# VLC_TX.net
KiCad netlist of a schematic drawn in Altium Designer
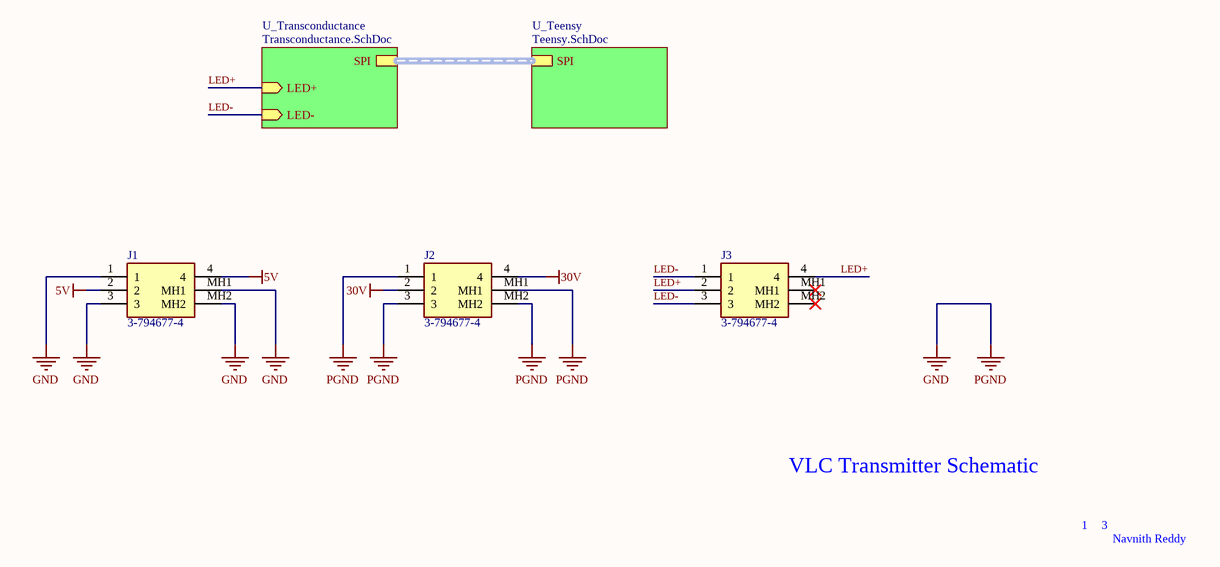
[diagram p0: VLC_TX.SchDoc]

(export (version "E")
  (design (tool "Eeschema 10.0.6"))
  (components
    (comp (ref "J1")
      (value "3-794677-4")
      (footprint "VLC_TX:37946774")
      (description "Connector")
      (fields (field (name "MOUSER PART NUMBER") "571-3-794677-4"))
      (libsource (lib "VLC_TX") (part "3-794677-4"))
    )
    (comp (ref "J2")
      (value "3-794677-4")
      (footprint "VLC_TX:37946774")
      (description "Connector")
      (fields (field (name "MOUSER PART NUMBER") "571-3-794677-4"))
      (libsource (lib "VLC_TX") (part "3-794677-4"))
    )
    (comp (ref "J3")
      (value "3-794677-4")
      (footprint "VLC_TX:37946774")
      (description "Connector")
      (fields (field (name "MOUSER PART NUMBER") "571-3-794677-4"))
      (libsource (lib "VLC_TX") (part "3-794677-4"))
    )
  )
  (nets
    (net (code "1") (name "/LED+") (class "Default")
      (node (ref "J3") (pin "2") (pinfunction "2_2") (pintype "passive"))
      (node (ref "J3") (pin "4") (pinfunction "4_4") (pintype "passive"))
    )
    (net (code "2") (name "/LED-") (class "Default")
      (node (ref "J3") (pin "1") (pinfunction "1_1") (pintype "passive"))
      (node (ref "J3") (pin "3") (pinfunction "3_3") (pintype "passive"))
    )
    (net (code "4") (name "5V") (class "Default")
      (node (ref "J1") (pin "2") (pinfunction "2_2") (pintype "passive"))
      (node (ref "J1") (pin "4") (pinfunction "4_4") (pintype "passive"))
    )
    (net (code "5") (name "30V") (class "Default")
      (node (ref "J2") (pin "2") (pinfunction "2_2") (pintype "passive"))
      (node (ref "J2") (pin "4") (pinfunction "4_4") (pintype "passive"))
    )
    (net (code "6") (name "GND") (class "Default")
      (node (ref "J1") (pin "1") (pinfunction "1_1") (pintype "passive"))
      (node (ref "J1") (pin "3") (pinfunction "3_3") (pintype "passive"))
      (node (ref "J1") (pin "MH1") (pinfunction "MH1_MH1") (pintype "passive"))
      (node (ref "J1") (pin "MH2") (pinfunction "MH2_MH2") (pintype "passive"))
      (node (ref "J2") (pin "1") (pinfunction "1_1") (pintype "passive"))
      (node (ref "J2") (pin "3") (pinfunction "3_3") (pintype "passive"))
      (node (ref "J2") (pin "MH1") (pinfunction "MH1_MH1") (pintype "passive"))
      (node (ref "J2") (pin "MH2") (pinfunction "MH2_MH2") (pintype "passive"))
    )
    (net (code "7") (name "unconnected-(J3-PadMH1)") (class "Default")
      (node (ref "J3") (pin "MH1") (pinfunction "MH1_MH1") (pintype "passive+no_connect"))
    )
    (net (code "8") (name "unconnected-(J3-PadMH2)") (class "Default")
      (node (ref "J3") (pin "MH2") (pinfunction "MH2_MH2") (pintype "passive+no_connect"))
    )
  )
)
